# LED.net
KiCad netlist of a schematic drawn in Altium Designer
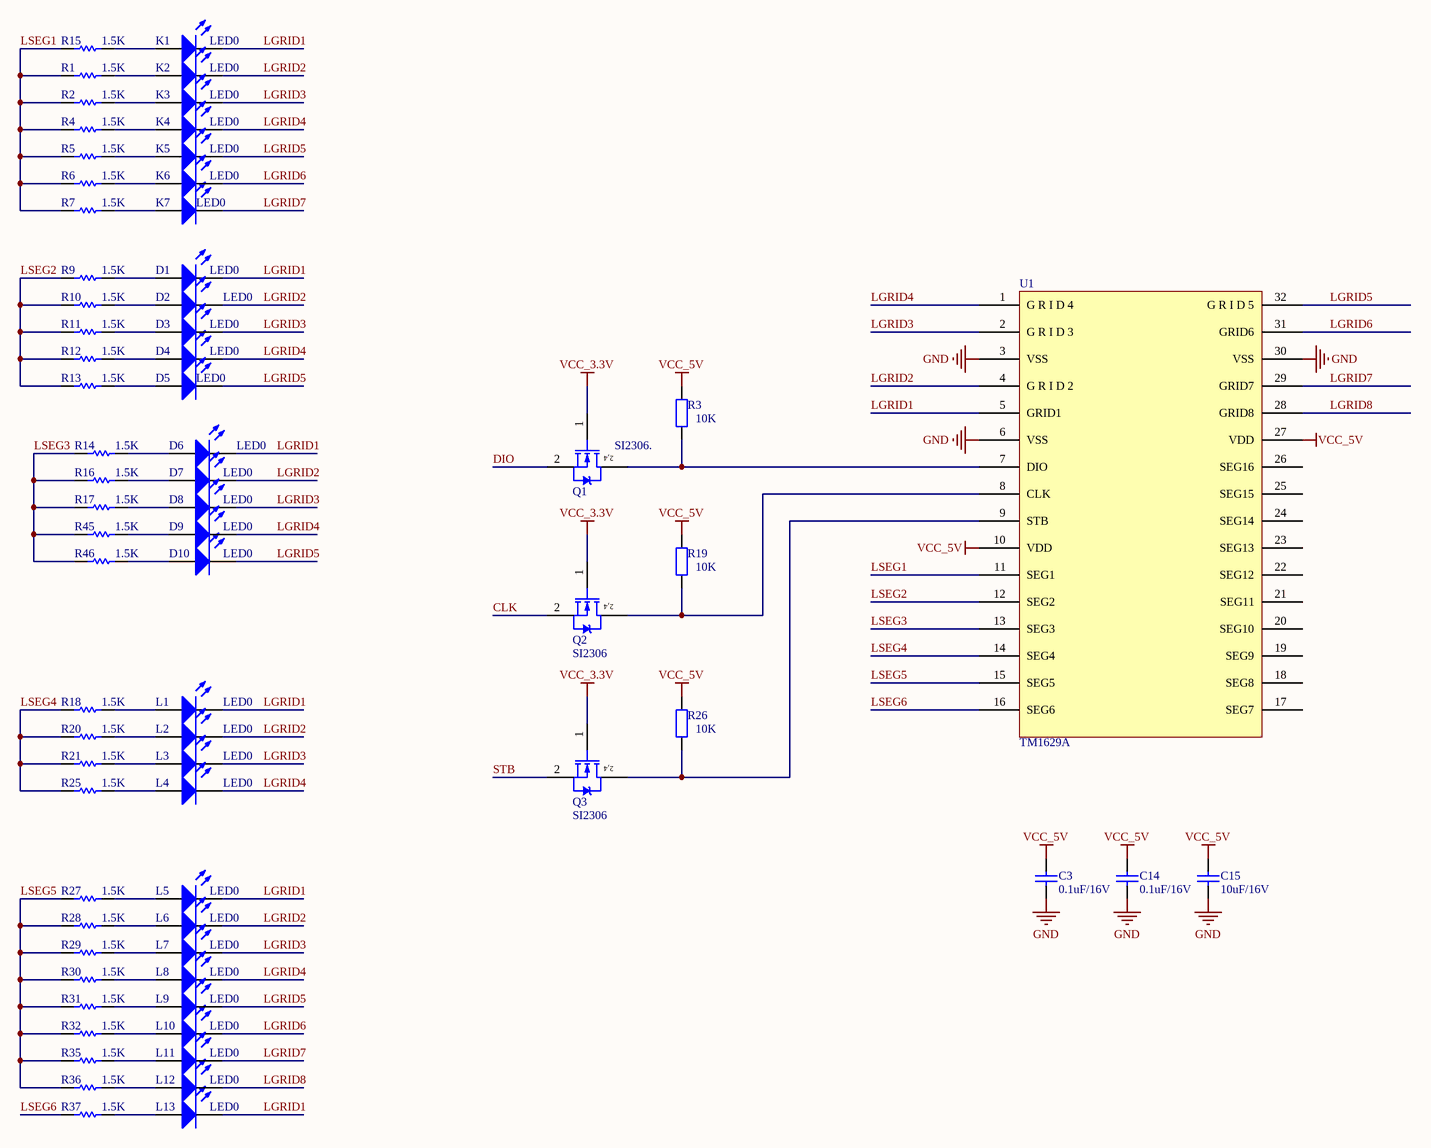
[diagram p0: LED.SchDoc]

(export (version "E")
  (design (tool "Eeschema 10.0.6"))
  (components
    (comp (ref "C3")
      (value "0.1uF/16V")
      (footprint "0603C")
      (description "Capacitor")
      (fields (field (name "PUBLISHER") "Altium Limited"))
      (libsource (lib "Miscellaneous Devices") (part "Cap"))
    )
    (comp (ref "C14")
      (value "0.1uF/16V")
      (footprint "0603C")
      (description "Capacitor")
      (fields (field (name "PUBLISHER") "Altium Limited"))
      (libsource (lib "Miscellaneous Devices") (part "Cap"))
    )
    (comp (ref "C15")
      (value "10uF/16V")
      (footprint "0603C")
      (description "Capacitor")
      (fields (field (name "PUBLISHER") "Altium Limited"))
      (libsource (lib "Miscellaneous Devices") (part "Cap"))
    )
    (comp (ref "D1")
      (value "LED0")
      (footprint "LED_DIP_257mm")
      (description "Typical INFRARED GaAs LED")
      (fields (field (name "PUBLISHER") "Altium Limited"))
      (libsource (lib "Miscellaneous Devices") (part "LED0"))
    )
    (comp (ref "D2")
      (value "LED0")
      (footprint "LED_DIP_257mm")
      (description "Typical INFRARED GaAs LED")
      (fields (field (name "PUBLISHER") "Altium Limited"))
      (libsource (lib "Miscellaneous Devices") (part "LED0"))
    )
    (comp (ref "D3")
      (value "LED0")
      (footprint "LED_DIP_257mm")
      (description "Typical INFRARED GaAs LED")
      (fields (field (name "PUBLISHER") "Altium Limited"))
      (libsource (lib "Miscellaneous Devices") (part "LED0"))
    )
    (comp (ref "D4")
      (value "LED0")
      (footprint "LED_DIP_257mm")
      (description "Typical INFRARED GaAs LED")
      (fields (field (name "PUBLISHER") "Altium Limited"))
      (libsource (lib "Miscellaneous Devices") (part "LED0"))
    )
    (comp (ref "D5")
      (value "LED0")
      (footprint "LED_DIP_257mm")
      (description "Typical INFRARED GaAs LED")
      (fields (field (name "PUBLISHER") "Altium Limited"))
      (libsource (lib "Miscellaneous Devices") (part "LED0"))
    )
    (comp (ref "D6")
      (value "LED0")
      (footprint "LED_DIP_257mm")
      (description "Typical INFRARED GaAs LED")
      (fields (field (name "PUBLISHER") "Altium Limited"))
      (libsource (lib "Miscellaneous Devices") (part "LED0"))
    )
    (comp (ref "D7")
      (value "LED0")
      (footprint "LED_DIP_257mm")
      (description "Typical INFRARED GaAs LED")
      (fields (field (name "PUBLISHER") "Altium Limited"))
      (libsource (lib "Miscellaneous Devices") (part "LED0"))
    )
    (comp (ref "D8")
      (value "LED0")
      (footprint "LED_DIP_257mm")
      (description "Typical INFRARED GaAs LED")
      (fields (field (name "PUBLISHER") "Altium Limited"))
      (libsource (lib "Miscellaneous Devices") (part "LED0"))
    )
    (comp (ref "D9")
      (value "LED0")
      (footprint "LED_DIP_257mm")
      (description "Typical INFRARED GaAs LED")
      (fields (field (name "PUBLISHER") "Altium Limited"))
      (libsource (lib "Miscellaneous Devices") (part "LED0"))
    )
    (comp (ref "D10")
      (value "LED0")
      (footprint "LED_DIP_257mm")
      (description "Typical INFRARED GaAs LED")
      (fields (field (name "PUBLISHER") "Altium Limited"))
      (libsource (lib "Miscellaneous Devices") (part "LED0"))
    )
    (comp (ref "K1")
      (value "LED0")
      (footprint "LED_DIP_5mm")
      (description "Typical INFRARED GaAs LED")
      (fields (field (name "PUBLISHER") "Altium Limited"))
      (libsource (lib "Miscellaneous Devices") (part "LED0"))
    )
    (comp (ref "K2")
      (value "LED0")
      (footprint "LED_DIP_5mm")
      (description "Typical INFRARED GaAs LED")
      (fields (field (name "PUBLISHER") "Altium Limited"))
      (libsource (lib "Miscellaneous Devices") (part "LED0"))
    )
    (comp (ref "K3")
      (value "LED0")
      (footprint "LED_DIP_5mm")
      (description "Typical INFRARED GaAs LED")
      (fields (field (name "PUBLISHER") "Altium Limited"))
      (libsource (lib "Miscellaneous Devices") (part "LED0"))
    )
    (comp (ref "K4")
      (value "LED0")
      (footprint "LED_DIP_5mm")
      (description "Typical INFRARED GaAs LED")
      (fields (field (name "PUBLISHER") "Altium Limited"))
      (libsource (lib "Miscellaneous Devices") (part "LED0"))
    )
    (comp (ref "K5")
      (value "LED0")
      (footprint "LED_DIP_5mm")
      (description "Typical INFRARED GaAs LED")
      (fields (field (name "PUBLISHER") "Altium Limited"))
      (libsource (lib "Miscellaneous Devices") (part "LED0"))
    )
    (comp (ref "K6")
      (value "LED0")
      (footprint "LED_DIP_5mm")
      (description "Typical INFRARED GaAs LED")
      (fields (field (name "PUBLISHER") "Altium Limited"))
      (libsource (lib "Miscellaneous Devices") (part "LED0"))
    )
    (comp (ref "K7")
      (value "LED0")
      (footprint "LED_DIP_5mm")
      (description "Typical INFRARED GaAs LED")
      (fields (field (name "PUBLISHER") "Altium Limited"))
      (libsource (lib "Miscellaneous Devices") (part "LED0"))
    )
    (comp (ref "L1")
      (value "LED0")
      (footprint "LED_DIP_5mm")
      (description "Typical INFRARED GaAs LED")
      (fields (field (name "PUBLISHER") "Altium Limited"))
      (libsource (lib "Miscellaneous Devices") (part "LED0"))
    )
    (comp (ref "L2")
      (value "LED0")
      (footprint "LED_DIP_5mm")
      (description "Typical INFRARED GaAs LED")
      (fields (field (name "PUBLISHER") "Altium Limited"))
      (libsource (lib "Miscellaneous Devices") (part "LED0"))
    )
    (comp (ref "L3")
      (value "LED0")
      (footprint "LED_DIP_5mm")
      (description "Typical INFRARED GaAs LED")
      (fields (field (name "PUBLISHER") "Altium Limited"))
      (libsource (lib "Miscellaneous Devices") (part "LED0"))
    )
    (comp (ref "L4")
      (value "LED0")
      (footprint "LED_DIP_5mm")
      (description "Typical INFRARED GaAs LED")
      (fields (field (name "PUBLISHER") "Altium Limited"))
      (libsource (lib "Miscellaneous Devices") (part "LED0"))
    )
    (comp (ref "L5")
      (value "LED0")
      (footprint "LED_DIP_257mm")
      (description "Typical INFRARED GaAs LED")
      (fields (field (name "PUBLISHER") "Altium Limited"))
      (libsource (lib "Miscellaneous Devices") (part "LED0"))
    )
    (comp (ref "L6")
      (value "LED0")
      (footprint "LED_DIP_257mm")
      (description "Typical INFRARED GaAs LED")
      (fields (field (name "PUBLISHER") "Altium Limited"))
      (libsource (lib "Miscellaneous Devices") (part "LED0"))
    )
    (comp (ref "L7")
      (value "LED0")
      (footprint "LED_DIP_257mm")
      (description "Typical INFRARED GaAs LED")
      (fields (field (name "PUBLISHER") "Altium Limited"))
      (libsource (lib "Miscellaneous Devices") (part "LED0"))
    )
    (comp (ref "L8")
      (value "LED0")
      (footprint "LED_DIP_257mm")
      (description "Typical INFRARED GaAs LED")
      (fields (field (name "PUBLISHER") "Altium Limited"))
      (libsource (lib "Miscellaneous Devices") (part "LED0"))
    )
    (comp (ref "L9")
      (value "LED0")
      (footprint "LED_DIP_257mm")
      (description "Typical INFRARED GaAs LED")
      (fields (field (name "PUBLISHER") "Altium Limited"))
      (libsource (lib "Miscellaneous Devices") (part "LED0"))
    )
    (comp (ref "L10")
      (value "LED0")
      (footprint "LED_DIP_257mm")
      (description "Typical INFRARED GaAs LED")
      (fields (field (name "PUBLISHER") "Altium Limited"))
      (libsource (lib "Miscellaneous Devices") (part "LED0"))
    )
    (comp (ref "L11")
      (value "LED0")
      (footprint "LED_DIP_257mm")
      (description "Typical INFRARED GaAs LED")
      (fields (field (name "PUBLISHER") "Altium Limited"))
      (libsource (lib "Miscellaneous Devices") (part "LED0"))
    )
    (comp (ref "L12")
      (value "LED0")
      (footprint "LED_DIP_257mm")
      (description "Typical INFRARED GaAs LED")
      (fields (field (name "PUBLISHER") "Altium Limited"))
      (libsource (lib "Miscellaneous Devices") (part "LED0"))
    )
    (comp (ref "L13")
      (value "LED0")
      (footprint "LED_DIP_257mm")
      (description "Typical INFRARED GaAs LED")
      (fields (field (name "PUBLISHER") "Altium Limited"))
      (libsource (lib "Miscellaneous Devices") (part "LED0"))
    )
    (comp (ref "Q1")
      (value "SI2306.")
      (footprint "SOT23-3")
      (description "BUK92150-55A")
      (fields (field (name "PUBLISHER") "Altium Limited"))
      (libsource (lib "Schlib1") (part "BUK92150-55A"))
    )
    (comp (ref "Q2")
      (value "SI2306")
      (footprint "SOT23-3")
      (description "BUK92150-55A")
      (fields (field (name "PUBLISHER") "Altium Limited"))
      (libsource (lib "Schlib1") (part "BUK92150-55A"))
    )
    (comp (ref "Q3")
      (value "SI2306")
      (footprint "SOT23-3")
      (description "BUK92150-55A")
      (fields (field (name "PUBLISHER") "Altium Limited"))
      (libsource (lib "Schlib1") (part "BUK92150-55A"))
    )
    (comp (ref "R1")
      (value "1.5K")
      (footprint "0603R")
      (description "Resistor")
      (fields (field (name "PUBLISHER") "Altium Limited"))
      (libsource (lib "Miscellaneous Devices") (part "Res1"))
    )
    (comp (ref "R2")
      (value "1.5K")
      (footprint "0603R")
      (description "Resistor")
      (fields (field (name "PUBLISHER") "Altium Limited"))
      (libsource (lib "Miscellaneous Devices") (part "Res1"))
    )
    (comp (ref "R3")
      (value "10K")
      (footprint "0603R")
      (description "Resistor")
      (fields (field (name "PUBLISHER") "Altium Limited"))
      (libsource (lib "Miscellaneous Devices") (part "Res2"))
    )
    (comp (ref "R4")
      (value "1.5K")
      (footprint "0603R")
      (description "Resistor")
      (fields (field (name "PUBLISHER") "Altium Limited"))
      (libsource (lib "Miscellaneous Devices") (part "Res1"))
    )
    (comp (ref "R5")
      (value "1.5K")
      (footprint "0603R")
      (description "Resistor")
      (fields (field (name "PUBLISHER") "Altium Limited"))
      (libsource (lib "Miscellaneous Devices") (part "Res1"))
    )
    (comp (ref "R6")
      (value "1.5K")
      (footprint "0603R")
      (description "Resistor")
      (fields (field (name "PUBLISHER") "Altium Limited"))
      (libsource (lib "Miscellaneous Devices") (part "Res1"))
    )
    (comp (ref "R7")
      (value "1.5K")
      (footprint "0603R")
      (description "Resistor")
      (fields (field (name "PUBLISHER") "Altium Limited"))
      (libsource (lib "Miscellaneous Devices") (part "Res1"))
    )
    (comp (ref "R9")
      (value "1.5K")
      (footprint "0603R")
      (description "Resistor")
      (fields (field (name "PUBLISHER") "Altium Limited"))
      (libsource (lib "Miscellaneous Devices") (part "Res1"))
    )
    (comp (ref "R10")
      (value "1.5K")
      (footprint "0603R")
      (description "Resistor")
      (fields (field (name "PUBLISHER") "Altium Limited"))
      (libsource (lib "Miscellaneous Devices") (part "Res1"))
    )
    (comp (ref "R11")
      (value "1.5K")
      (footprint "0603R")
      (description "Resistor")
      (fields (field (name "PUBLISHER") "Altium Limited"))
      (libsource (lib "Miscellaneous Devices") (part "Res1"))
    )
    (comp (ref "R12")
      (value "1.5K")
      (footprint "0603R")
      (description "Resistor")
      (fields (field (name "PUBLISHER") "Altium Limited"))
      (libsource (lib "Miscellaneous Devices") (part "Res1"))
    )
    (comp (ref "R13")
      (value "1.5K")
      (footprint "0603R")
      (description "Resistor")
      (fields (field (name "PUBLISHER") "Altium Limited"))
      (libsource (lib "Miscellaneous Devices") (part "Res1"))
    )
    (comp (ref "R14")
      (value "1.5K")
      (footprint "0603R")
      (description "Resistor")
      (fields (field (name "PUBLISHER") "Altium Limited"))
      (libsource (lib "Miscellaneous Devices") (part "Res1"))
    )
    (comp (ref "R15")
      (value "1.5K")
      (footprint "0603R")
      (description "Resistor")
      (fields (field (name "PUBLISHER") "Altium Limited"))
      (libsource (lib "Miscellaneous Devices") (part "Res1"))
    )
    (comp (ref "R16")
      (value "1.5K")
      (footprint "0603R")
      (description "Resistor")
      (fields (field (name "PUBLISHER") "Altium Limited"))
      (libsource (lib "Miscellaneous Devices") (part "Res1"))
    )
    (comp (ref "R17")
      (value "1.5K")
      (footprint "0603R")
      (description "Resistor")
      (fields (field (name "PUBLISHER") "Altium Limited"))
      (libsource (lib "Miscellaneous Devices") (part "Res1"))
    )
    (comp (ref "R18")
      (value "1.5K")
      (footprint "0603R")
      (description "Resistor")
      (fields (field (name "PUBLISHER") "Altium Limited"))
      (libsource (lib "Miscellaneous Devices") (part "Res1"))
    )
    (comp (ref "R19")
      (value "10K")
      (footprint "0603R")
      (description "Resistor")
      (fields (field (name "PUBLISHER") "Altium Limited"))
      (libsource (lib "Miscellaneous Devices") (part "Res2"))
    )
    (comp (ref "R20")
      (value "1.5K")
      (footprint "0603R")
      (description "Resistor")
      (fields (field (name "PUBLISHER") "Altium Limited"))
      (libsource (lib "Miscellaneous Devices") (part "Res1"))
    )
    (comp (ref "R21")
      (value "1.5K")
      (footprint "0603R")
      (description "Resistor")
      (fields (field (name "PUBLISHER") "Altium Limited"))
      (libsource (lib "Miscellaneous Devices") (part "Res1"))
    )
    (comp (ref "R25")
      (value "1.5K")
      (footprint "0603R")
      (description "Resistor")
      (fields (field (name "PUBLISHER") "Altium Limited"))
      (libsource (lib "Miscellaneous Devices") (part "Res1"))
    )
    (comp (ref "R26")
      (value "10K")
      (footprint "0603R")
      (description "Resistor")
      (fields (field (name "PUBLISHER") "Altium Limited"))
      (libsource (lib "Miscellaneous Devices") (part "Res2"))
    )
    (comp (ref "R27")
      (value "1.5K")
      (footprint "0603R")
      (description "Resistor")
      (fields (field (name "PUBLISHER") "Altium Limited"))
      (libsource (lib "Miscellaneous Devices") (part "Res1"))
    )
    (comp (ref "R28")
      (value "1.5K")
      (footprint "0603R")
      (description "Resistor")
      (fields (field (name "PUBLISHER") "Altium Limited"))
      (libsource (lib "Miscellaneous Devices") (part "Res1"))
    )
    (comp (ref "R29")
      (value "1.5K")
      (footprint "0603R")
      (description "Resistor")
      (fields (field (name "PUBLISHER") "Altium Limited"))
      (libsource (lib "Miscellaneous Devices") (part "Res1"))
    )
    (comp (ref "R30")
      (value "1.5K")
      (footprint "0603R")
      (description "Resistor")
      (fields (field (name "PUBLISHER") "Altium Limited"))
      (libsource (lib "Miscellaneous Devices") (part "Res1"))
    )
    (comp (ref "R31")
      (value "1.5K")
      (footprint "0603R")
      (description "Resistor")
      (fields (field (name "PUBLISHER") "Altium Limited"))
      (libsource (lib "Miscellaneous Devices") (part "Res1"))
    )
    (comp (ref "R32")
      (value "1.5K")
      (footprint "0603R")
      (description "Resistor")
      (fields (field (name "PUBLISHER") "Altium Limited"))
      (libsource (lib "Miscellaneous Devices") (part "Res1"))
    )
    (comp (ref "R35")
      (value "1.5K")
      (footprint "0603R")
      (description "Resistor")
      (fields (field (name "PUBLISHER") "Altium Limited"))
      (libsource (lib "Miscellaneous Devices") (part "Res1"))
    )
    (comp (ref "R36")
      (value "1.5K")
      (footprint "0603R")
      (description "Resistor")
      (fields (field (name "PUBLISHER") "Altium Limited"))
      (libsource (lib "Miscellaneous Devices") (part "Res1"))
    )
    (comp (ref "R37")
      (value "1.5K")
      (footprint "0603R")
      (description "Resistor")
      (fields (field (name "PUBLISHER") "Altium Limited"))
      (libsource (lib "Miscellaneous Devices") (part "Res1"))
    )
    (comp (ref "R45")
      (value "1.5K")
      (footprint "0603R")
      (description "Resistor")
      (fields (field (name "PUBLISHER") "Altium Limited"))
      (libsource (lib "Miscellaneous Devices") (part "Res1"))
    )
    (comp (ref "R46")
      (value "1.5K")
      (footprint "0603R")
      (description "Resistor")
      (fields (field (name "PUBLISHER") "Altium Limited"))
      (libsource (lib "Miscellaneous Devices") (part "Res1"))
    )
    (comp (ref "U1")
      (value "TM1629A")
      (footprint "SOP127P1040X265-32N")
      (libsource (lib "Schlib_20110825") (part "TM1629A"))
    )
  )
  (nets
    (net (code "1") (name "/CLK") (class "Default")
      (node (ref "Q2") (pin "2") (pinfunction "S_2") (pintype "passive"))
    )
    (net (code "2") (name "/DIO") (class "Default")
      (node (ref "Q1") (pin "2") (pinfunction "S_2") (pintype "passive"))
    )
    (net (code "3") (name "/LGRID1") (class "Default")
      (node (ref "D1") (pin "2") (pinfunction "K_2") (pintype "passive"))
      (node (ref "D6") (pin "2") (pinfunction "K_2") (pintype "passive"))
      (node (ref "K1") (pin "2") (pinfunction "K_2") (pintype "passive"))
      (node (ref "L1") (pin "2") (pinfunction "K_2") (pintype "passive"))
      (node (ref "L13") (pin "2") (pinfunction "K_2") (pintype "passive"))
      (node (ref "L5") (pin "2") (pinfunction "K_2") (pintype "passive"))
      (node (ref "U1") (pin "5") (pinfunction "GRID1_5") (pintype "passive"))
    )
    (net (code "4") (name "/LGRID2") (class "Default")
      (node (ref "D2") (pin "2") (pinfunction "K_2") (pintype "passive"))
      (node (ref "D7") (pin "2") (pinfunction "K_2") (pintype "passive"))
      (node (ref "K2") (pin "2") (pinfunction "K_2") (pintype "passive"))
      (node (ref "L2") (pin "2") (pinfunction "K_2") (pintype "passive"))
      (node (ref "L6") (pin "2") (pinfunction "K_2") (pintype "passive"))
      (node (ref "U1") (pin "4") (pinfunction "G_R_I_D_2_4") (pintype "passive"))
    )
    (net (code "5") (name "/LGRID3") (class "Default")
      (node (ref "D3") (pin "2") (pinfunction "K_2") (pintype "passive"))
      (node (ref "D8") (pin "2") (pinfunction "K_2") (pintype "passive"))
      (node (ref "K3") (pin "2") (pinfunction "K_2") (pintype "passive"))
      (node (ref "L3") (pin "2") (pinfunction "K_2") (pintype "passive"))
      (node (ref "L7") (pin "2") (pinfunction "K_2") (pintype "passive"))
      (node (ref "U1") (pin "2") (pinfunction "G_R_I_D_3_2") (pintype "passive"))
    )
    (net (code "6") (name "/LGRID4") (class "Default")
      (node (ref "D4") (pin "2") (pinfunction "K_2") (pintype "passive"))
      (node (ref "D9") (pin "2") (pinfunction "K_2") (pintype "passive"))
      (node (ref "K4") (pin "2") (pinfunction "K_2") (pintype "passive"))
      (node (ref "L4") (pin "2") (pinfunction "K_2") (pintype "passive"))
      (node (ref "L8") (pin "2") (pinfunction "K_2") (pintype "passive"))
      (node (ref "U1") (pin "1") (pinfunction "G_R_I_D_4_1") (pintype "passive"))
    )
    (net (code "7") (name "/LGRID5") (class "Default")
      (node (ref "D10") (pin "2") (pinfunction "K_2") (pintype "passive"))
      (node (ref "D5") (pin "2") (pinfunction "K_2") (pintype "passive"))
      (node (ref "K5") (pin "2") (pinfunction "K_2") (pintype "passive"))
      (node (ref "L9") (pin "2") (pinfunction "K_2") (pintype "passive"))
      (node (ref "U1") (pin "32") (pinfunction "G_R_I_D_5_32") (pintype "passive"))
    )
    (net (code "8") (name "/LGRID6") (class "Default")
      (node (ref "K6") (pin "2") (pinfunction "K_2") (pintype "passive"))
      (node (ref "L10") (pin "2") (pinfunction "K_2") (pintype "passive"))
      (node (ref "U1") (pin "31") (pinfunction "GRID6_31") (pintype "passive"))
    )
    (net (code "9") (name "/LGRID7") (class "Default")
      (node (ref "K7") (pin "2") (pinfunction "K_2") (pintype "passive"))
      (node (ref "L11") (pin "2") (pinfunction "K_2") (pintype "passive"))
      (node (ref "U1") (pin "29") (pinfunction "GRID7_29") (pintype "passive"))
    )
    (net (code "10") (name "/LGRID8") (class "Default")
      (node (ref "L12") (pin "2") (pinfunction "K_2") (pintype "passive"))
      (node (ref "U1") (pin "28") (pinfunction "GRID8_28") (pintype "passive"))
    )
    (net (code "11") (name "/LSEG1") (class "Default")
      (node (ref "R1") (pin "2") (pinfunction "2_2") (pintype "passive"))
      (node (ref "R15") (pin "2") (pinfunction "2_2") (pintype "passive"))
      (node (ref "R2") (pin "2") (pinfunction "2_2") (pintype "passive"))
      (node (ref "R4") (pin "2") (pinfunction "2_2") (pintype "passive"))
      (node (ref "R5") (pin "2") (pinfunction "2_2") (pintype "passive"))
      (node (ref "R6") (pin "2") (pinfunction "2_2") (pintype "passive"))
      (node (ref "R7") (pin "2") (pinfunction "2_2") (pintype "passive"))
      (node (ref "U1") (pin "11") (pinfunction "SEG1_11") (pintype "passive"))
    )
    (net (code "12") (name "/LSEG2") (class "Default")
      (node (ref "R10") (pin "2") (pinfunction "2_2") (pintype "passive"))
      (node (ref "R11") (pin "2") (pinfunction "2_2") (pintype "passive"))
      (node (ref "R12") (pin "2") (pinfunction "2_2") (pintype "passive"))
      (node (ref "R13") (pin "2") (pinfunction "2_2") (pintype "passive"))
      (node (ref "R9") (pin "2") (pinfunction "2_2") (pintype "passive"))
      (node (ref "U1") (pin "12") (pinfunction "SEG2_12") (pintype "passive"))
    )
    (net (code "13") (name "/LSEG3") (class "Default")
      (node (ref "R14") (pin "2") (pinfunction "2_2") (pintype "passive"))
      (node (ref "R16") (pin "2") (pinfunction "2_2") (pintype "passive"))
      (node (ref "R17") (pin "2") (pinfunction "2_2") (pintype "passive"))
      (node (ref "R45") (pin "2") (pinfunction "2_2") (pintype "passive"))
      (node (ref "R46") (pin "2") (pinfunction "2_2") (pintype "passive"))
      (node (ref "U1") (pin "13") (pinfunction "SEG3_13") (pintype "passive"))
    )
    (net (code "14") (name "/LSEG4") (class "Default")
      (node (ref "R18") (pin "2") (pinfunction "2_2") (pintype "passive"))
      (node (ref "R20") (pin "2") (pinfunction "2_2") (pintype "passive"))
      (node (ref "R21") (pin "2") (pinfunction "2_2") (pintype "passive"))
      (node (ref "R25") (pin "2") (pinfunction "2_2") (pintype "passive"))
      (node (ref "U1") (pin "14") (pinfunction "SEG4_14") (pintype "passive"))
    )
    (net (code "15") (name "/LSEG5") (class "Default")
      (node (ref "R27") (pin "2") (pinfunction "2_2") (pintype "passive"))
      (node (ref "R28") (pin "2") (pinfunction "2_2") (pintype "passive"))
      (node (ref "R29") (pin "2") (pinfunction "2_2") (pintype "passive"))
      (node (ref "R30") (pin "2") (pinfunction "2_2") (pintype "passive"))
      (node (ref "R31") (pin "2") (pinfunction "2_2") (pintype "passive"))
      (node (ref "R32") (pin "2") (pinfunction "2_2") (pintype "passive"))
      (node (ref "R35") (pin "2") (pinfunction "2_2") (pintype "passive"))
      (node (ref "R36") (pin "2") (pinfunction "2_2") (pintype "passive"))
      (node (ref "U1") (pin "15") (pinfunction "SEG5_15") (pintype "passive"))
    )
    (net (code "16") (name "/LSEG6") (class "Default")
      (node (ref "R37") (pin "2") (pinfunction "2_2") (pintype "passive"))
      (node (ref "U1") (pin "16") (pinfunction "SEG6_16") (pintype "passive"))
    )
    (net (code "17") (name "/STB") (class "Default")
      (node (ref "Q3") (pin "2") (pinfunction "S_2") (pintype "passive"))
    )
    (net (code "18") (name "GND") (class "Default")
      (node (ref "C14") (pin "2") (pinfunction "2_2") (pintype "passive"))
      (node (ref "C15") (pin "2") (pinfunction "2_2") (pintype "passive"))
      (node (ref "C3") (pin "2") (pinfunction "2_2") (pintype "passive"))
      (node (ref "U1") (pin "3") (pinfunction "VSS_3") (pintype "passive"))
      (node (ref "U1") (pin "30") (pinfunction "VSS_30") (pintype "passive"))
      (node (ref "U1") (pin "6") (pinfunction "VSS_6") (pintype "passive"))
    )
    (net (code "19") (name "Net-(D1-A)") (class "Default")
      (node (ref "D1") (pin "1") (pinfunction "A_1") (pintype "passive"))
      (node (ref "R9") (pin "1") (pinfunction "1_1") (pintype "passive"))
    )
    (net (code "20") (name "Net-(D2-A)") (class "Default")
      (node (ref "D2") (pin "1") (pinfunction "A_1") (pintype "passive"))
      (node (ref "R10") (pin "1") (pinfunction "1_1") (pintype "passive"))
    )
    (net (code "21") (name "Net-(D3-A)") (class "Default")
      (node (ref "D3") (pin "1") (pinfunction "A_1") (pintype "passive"))
      (node (ref "R11") (pin "1") (pinfunction "1_1") (pintype "passive"))
    )
    (net (code "22") (name "Net-(D4-A)") (class "Default")
      (node (ref "D4") (pin "1") (pinfunction "A_1") (pintype "passive"))
      (node (ref "R12") (pin "1") (pinfunction "1_1") (pintype "passive"))
    )
    (net (code "23") (name "Net-(D5-A)") (class "Default")
      (node (ref "D5") (pin "1") (pinfunction "A_1") (pintype "passive"))
      (node (ref "R13") (pin "1") (pinfunction "1_1") (pintype "passive"))
    )
    (net (code "24") (name "Net-(D6-A)") (class "Default")
      (node (ref "D6") (pin "1") (pinfunction "A_1") (pintype "passive"))
      (node (ref "R14") (pin "1") (pinfunction "1_1") (pintype "passive"))
    )
    (net (code "25") (name "Net-(D7-A)") (class "Default")
      (node (ref "D7") (pin "1") (pinfunction "A_1") (pintype "passive"))
      (node (ref "R16") (pin "1") (pinfunction "1_1") (pintype "passive"))
    )
    (net (code "26") (name "Net-(D8-A)") (class "Default")
      (node (ref "D8") (pin "1") (pinfunction "A_1") (pintype "passive"))
      (node (ref "R17") (pin "1") (pinfunction "1_1") (pintype "passive"))
    )
    (net (code "27") (name "Net-(D9-A)") (class "Default")
      (node (ref "D9") (pin "1") (pinfunction "A_1") (pintype "passive"))
      (node (ref "R45") (pin "1") (pinfunction "1_1") (pintype "passive"))
    )
    (net (code "28") (name "Net-(D10-A)") (class "Default")
      (node (ref "D10") (pin "1") (pinfunction "A_1") (pintype "passive"))
      (node (ref "R46") (pin "1") (pinfunction "1_1") (pintype "passive"))
    )
    (net (code "29") (name "Net-(K1-A)") (class "Default")
      (node (ref "K1") (pin "1") (pinfunction "A_1") (pintype "passive"))
      (node (ref "R15") (pin "1") (pinfunction "1_1") (pintype "passive"))
    )
    (net (code "30") (name "Net-(K2-A)") (class "Default")
      (node (ref "K2") (pin "1") (pinfunction "A_1") (pintype "passive"))
      (node (ref "R1") (pin "1") (pinfunction "1_1") (pintype "passive"))
    )
    (net (code "31") (name "Net-(K3-A)") (class "Default")
      (node (ref "K3") (pin "1") (pinfunction "A_1") (pintype "passive"))
      (node (ref "R2") (pin "1") (pinfunction "1_1") (pintype "passive"))
    )
    (net (code "32") (name "Net-(K4-A)") (class "Default")
      (node (ref "K4") (pin "1") (pinfunction "A_1") (pintype "passive"))
      (node (ref "R4") (pin "1") (pinfunction "1_1") (pintype "passive"))
    )
    (net (code "33") (name "Net-(K5-A)") (class "Default")
      (node (ref "K5") (pin "1") (pinfunction "A_1") (pintype "passive"))
      (node (ref "R5") (pin "1") (pinfunction "1_1") (pintype "passive"))
    )
    (net (code "34") (name "Net-(K6-A)") (class "Default")
      (node (ref "K6") (pin "1") (pinfunction "A_1") (pintype "passive"))
      (node (ref "R6") (pin "1") (pinfunction "1_1") (pintype "passive"))
    )
    (net (code "35") (name "Net-(K7-A)") (class "Default")
      (node (ref "K7") (pin "1") (pinfunction "A_1") (pintype "passive"))
      (node (ref "R7") (pin "1") (pinfunction "1_1") (pintype "passive"))
    )
    (net (code "36") (name "Net-(L1-A)") (class "Default")
      (node (ref "L1") (pin "1") (pinfunction "A_1") (pintype "passive"))
      (node (ref "R18") (pin "1") (pinfunction "1_1") (pintype "passive"))
    )
    (net (code "37") (name "Net-(L2-A)") (class "Default")
      (node (ref "L2") (pin "1") (pinfunction "A_1") (pintype "passive"))
      (node (ref "R20") (pin "1") (pinfunction "1_1") (pintype "passive"))
    )
    (net (code "38") (name "Net-(L3-A)") (class "Default")
      (node (ref "L3") (pin "1") (pinfunction "A_1") (pintype "passive"))
      (node (ref "R21") (pin "1") (pinfunction "1_1") (pintype "passive"))
    )
    (net (code "39") (name "Net-(L4-A)") (class "Default")
      (node (ref "L4") (pin "1") (pinfunction "A_1") (pintype "passive"))
      (node (ref "R25") (pin "1") (pinfunction "1_1") (pintype "passive"))
    )
    (net (code "40") (name "Net-(L5-A)") (class "Default")
      (node (ref "L5") (pin "1") (pinfunction "A_1") (pintype "passive"))
      (node (ref "R27") (pin "1") (pinfunction "1_1") (pintype "passive"))
    )
    (net (code "41") (name "Net-(L6-A)") (class "Default")
      (node (ref "L6") (pin "1") (pinfunction "A_1") (pintype "passive"))
      (node (ref "R28") (pin "1") (pinfunction "1_1") (pintype "passive"))
    )
    (net (code "42") (name "Net-(L7-A)") (class "Default")
      (node (ref "L7") (pin "1") (pinfunction "A_1") (pintype "passive"))
      (node (ref "R29") (pin "1") (pinfunction "1_1") (pintype "passive"))
    )
    (net (code "43") (name "Net-(L8-A)") (class "Default")
      (node (ref "L8") (pin "1") (pinfunction "A_1") (pintype "passive"))
      (node (ref "R30") (pin "1") (pinfunction "1_1") (pintype "passive"))
    )
    (net (code "44") (name "Net-(L9-A)") (class "Default")
      (node (ref "L9") (pin "1") (pinfunction "A_1") (pintype "passive"))
      (node (ref "R31") (pin "1") (pinfunction "1_1") (pintype "passive"))
    )
    (net (code "45") (name "Net-(L10-A)") (class "Default")
      (node (ref "L10") (pin "1") (pinfunction "A_1") (pintype "passive"))
      (node (ref "R32") (pin "1") (pinfunction "1_1") (pintype "passive"))
    )
    (net (code "46") (name "Net-(L11-A)") (class "Default")
      (node (ref "L11") (pin "1") (pinfunction "A_1") (pintype "passive"))
      (node (ref "R35") (pin "1") (pinfunction "1_1") (pintype "passive"))
    )
    (net (code "47") (name "Net-(L12-A)") (class "Default")
      (node (ref "L12") (pin "1") (pinfunction "A_1") (pintype "passive"))
      (node (ref "R36") (pin "1") (pinfunction "1_1") (pintype "passive"))
    )
    (net (code "48") (name "Net-(L13-A)") (class "Default")
      (node (ref "L13") (pin "1") (pinfunction "A_1") (pintype "passive"))
      (node (ref "R37") (pin "1") (pinfunction "1_1") (pintype "passive"))
    )
    (net (code "49") (name "Net-(Q1-D)") (class "Default")
      (node (ref "Q1") (pin "3") (pinfunction "D_3") (pintype "passive"))
      (node (ref "R3") (pin "2") (pinfunction "2_2") (pintype "passive"))
      (node (ref "U1") (pin "7") (pinfunction "DIO_7") (pintype "passive"))
    )
    (net (code "50") (name "Net-(Q2-D)") (class "Default")
      (node (ref "Q2") (pin "3") (pinfunction "D_3") (pintype "passive"))
      (node (ref "R19") (pin "2") (pinfunction "2_2") (pintype "passive"))
      (node (ref "U1") (pin "8") (pinfunction "CLK_8") (pintype "passive"))
    )
    (net (code "51") (name "Net-(Q3-D)") (class "Default")
      (node (ref "Q3") (pin "3") (pinfunction "D_3") (pintype "passive"))
      (node (ref "R26") (pin "2") (pinfunction "2_2") (pintype "passive"))
      (node (ref "U1") (pin "9") (pinfunction "STB_9") (pintype "passive"))
    )
    (net (code "52") (name "VCC_3.3V") (class "Default")
      (node (ref "Q1") (pin "1") (pinfunction "G_1") (pintype "passive"))
      (node (ref "Q2") (pin "1") (pinfunction "G_1") (pintype "passive"))
      (node (ref "Q3") (pin "1") (pinfunction "G_1") (pintype "passive"))
    )
    (net (code "53") (name "VCC_5V") (class "Default")
      (node (ref "C14") (pin "1") (pinfunction "1_1") (pintype "passive"))
      (node (ref "C15") (pin "1") (pinfunction "1_1") (pintype "passive"))
      (node (ref "C3") (pin "1") (pinfunction "1_1") (pintype "passive"))
      (node (ref "R19") (pin "1") (pinfunction "1_1") (pintype "passive"))
      (node (ref "R26") (pin "1") (pinfunction "1_1") (pintype "passive"))
      (node (ref "R3") (pin "1") (pinfunction "1_1") (pintype "passive"))
      (node (ref "U1") (pin "10") (pinfunction "VDD_10") (pintype "passive"))
      (node (ref "U1") (pin "27") (pinfunction "VDD_27") (pintype "passive"))
    )
    (net (code "54") (name "unconnected-(U1-SEG7-Pad17)") (class "Default")
      (node (ref "U1") (pin "17") (pinfunction "SEG7_17") (pintype "passive"))
    )
    (net (code "55") (name "unconnected-(U1-SEG8-Pad18)") (class "Default")
      (node (ref "U1") (pin "18") (pinfunction "SEG8_18") (pintype "passive"))
    )
    (net (code "56") (name "unconnected-(U1-SEG9-Pad19)") (class "Default")
      (node (ref "U1") (pin "19") (pinfunction "SEG9_19") (pintype "passive"))
    )
    (net (code "57") (name "unconnected-(U1-SEG10-Pad20)") (class "Default")
      (node (ref "U1") (pin "20") (pinfunction "SEG10_20") (pintype "passive"))
    )
    (net (code "58") (name "unconnected-(U1-SEG11-Pad21)") (class "Default")
      (node (ref "U1") (pin "21") (pinfunction "SEG11_21") (pintype "passive"))
    )
    (net (code "59") (name "unconnected-(U1-SEG12-Pad22)") (class "Default")
      (node (ref "U1") (pin "22") (pinfunction "SEG12_22") (pintype "passive"))
    )
    (net (code "60") (name "unconnected-(U1-SEG13-Pad23)") (class "Default")
      (node (ref "U1") (pin "23") (pinfunction "SEG13_23") (pintype "passive"))
    )
    (net (code "61") (name "unconnected-(U1-SEG14-Pad24)") (class "Default")
      (node (ref "U1") (pin "24") (pinfunction "SEG14_24") (pintype "passive"))
    )
    (net (code "62") (name "unconnected-(U1-SEG15-Pad25)") (class "Default")
      (node (ref "U1") (pin "25") (pinfunction "SEG15_25") (pintype "passive"))
    )
    (net (code "63") (name "unconnected-(U1-SEG16-Pad26)") (class "Default")
      (node (ref "U1") (pin "26") (pinfunction "SEG16_26") (pintype "passive"))
    )
  )
)
